# xbee_inclinometer.net
KiCad netlist of a schematic drawn in EAGLE
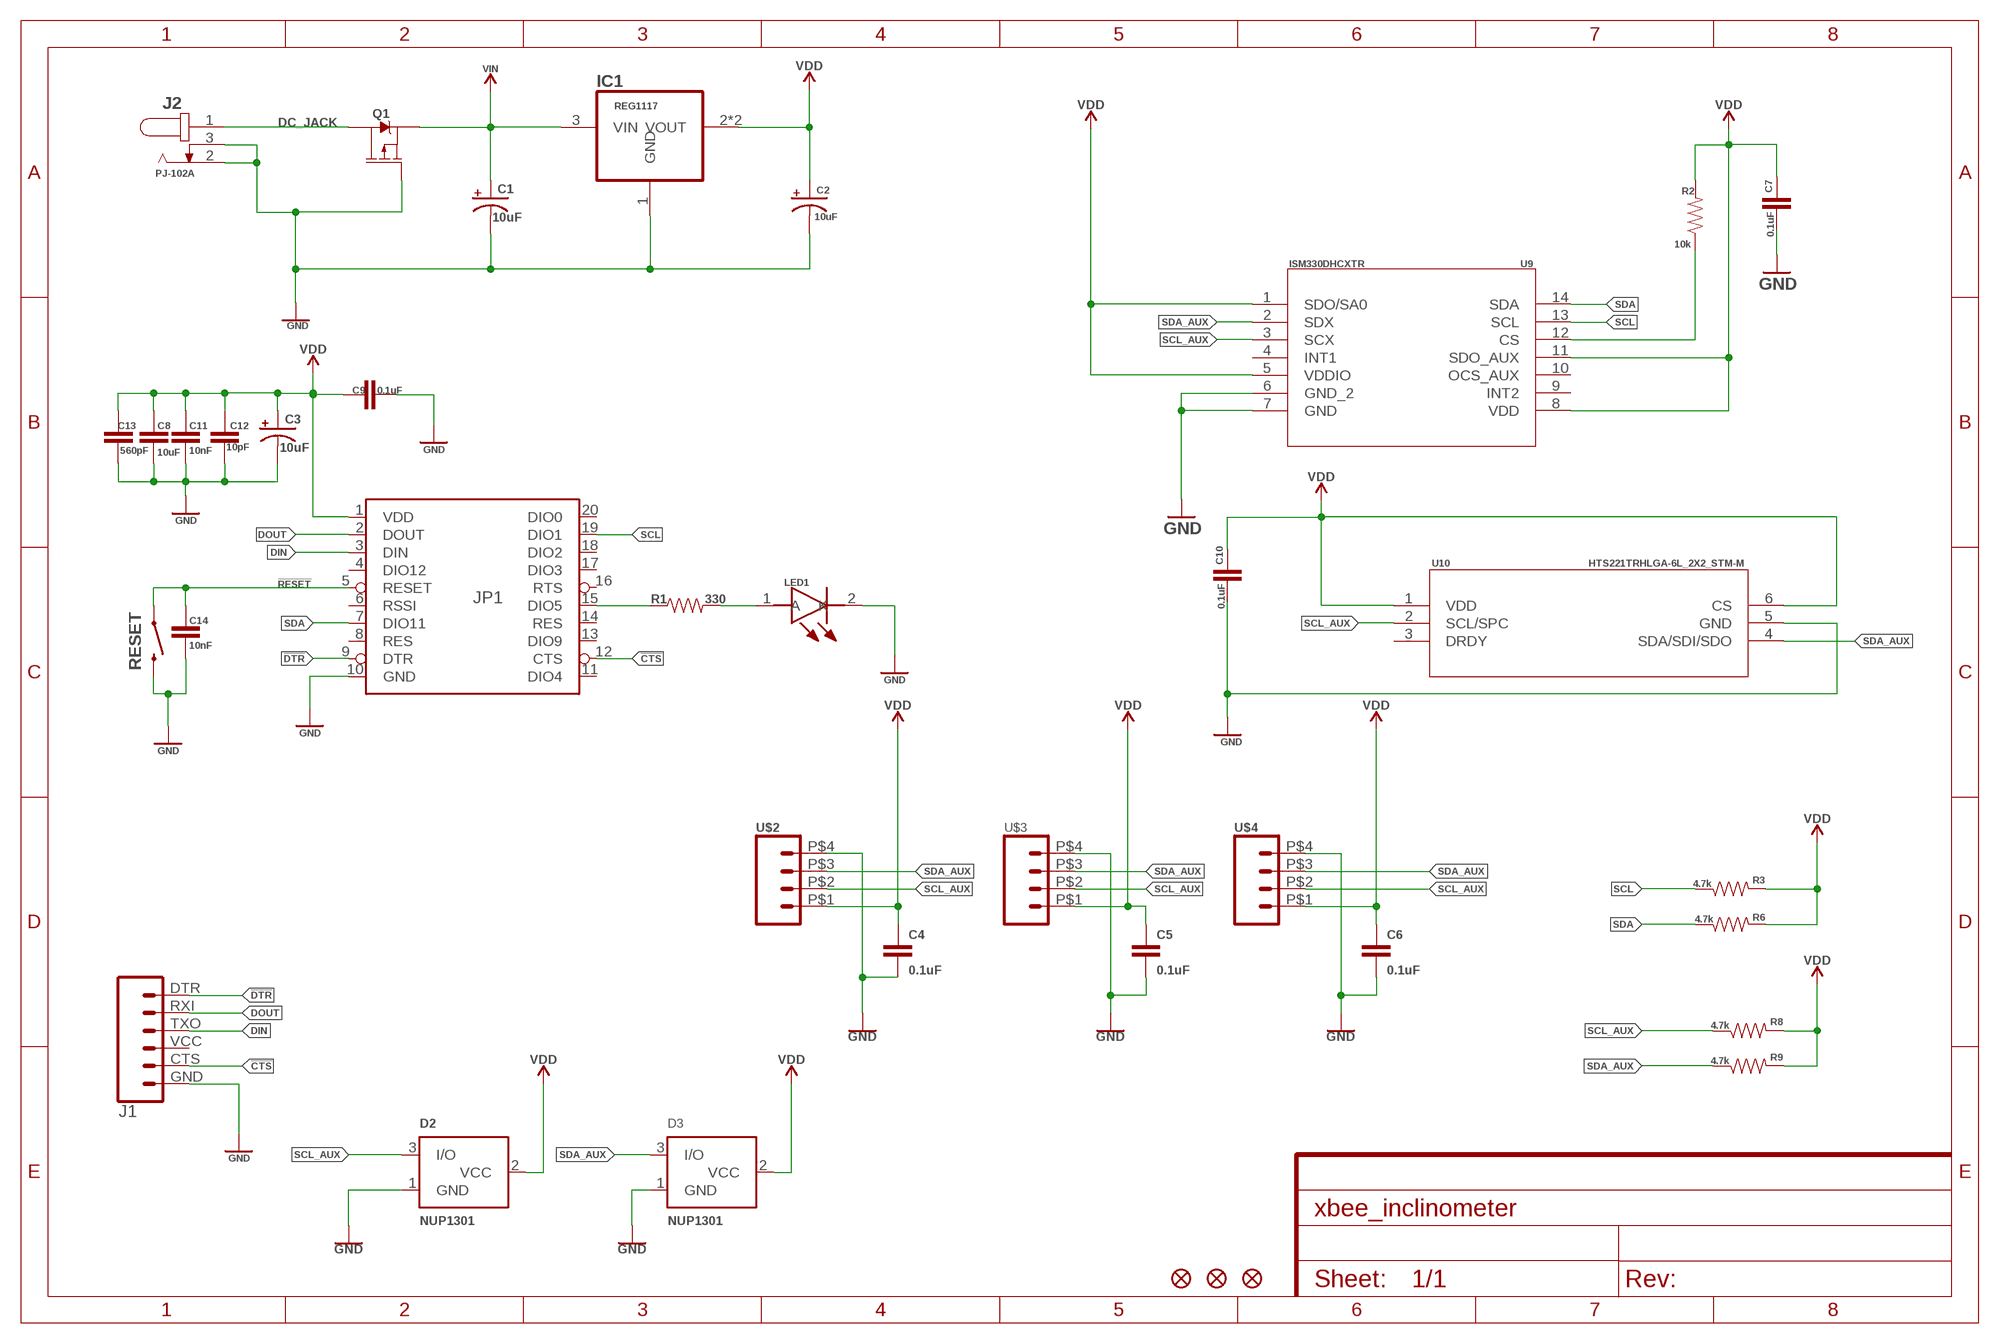
[diagram p0: schematic, sheet 1]

(export (version "E")
  (design (tool "Eeschema 10.0.6"))
  (components
    (comp (ref "C1")
      (value "10uF")
      (footprint "eagle-import:EIA3216")
      (libsource (lib "eagle-import") (part "10UF-POLAR-EIA3216-16V-10%(TANT)"))
    )
    (comp (ref "C2")
      (value "10uF")
      (footprint "eagle-import:EIA3216")
      (libsource (lib "eagle-import") (part "10UF-POLAR-EIA3216-16V-10%(TANT)"))
    )
    (comp (ref "C3")
      (value "10uF")
      (footprint "eagle-import:EIA3216")
      (libsource (lib "eagle-import") (part "10UF-POLAR-EIA3216-16V-10%(TANT)"))
    )
    (comp (ref "C4")
      (value "0.1uF")
      (footprint "eagle-import:0603")
      (libsource (lib "eagle-import") (part "0.1UF-0603-25V-(+80/-20%)"))
    )
    (comp (ref "C5")
      (value "0.1uF")
      (footprint "eagle-import:0603")
      (libsource (lib "eagle-import") (part "0.1UF-0603-25V-(+80/-20%)"))
    )
    (comp (ref "C6")
      (value "0.1uF")
      (footprint "eagle-import:0603")
      (libsource (lib "eagle-import") (part "0.1UF-0603-25V-(+80/-20%)"))
    )
    (comp (ref "C7")
      (value "0.1uF")
      (footprint "eagle-import:0603")
      (libsource (lib "eagle-import") (part "0.1UF-0603-25V-(+80/-20%)"))
    )
    (comp (ref "C8")
      (value "10uF")
      (footprint "eagle-import:0603")
      (libsource (lib "eagle-import") (part "10UF-0603-6.3V-20%"))
    )
    (comp (ref "C9")
      (value "0.1uF")
      (footprint "eagle-import:0603")
      (libsource (lib "eagle-import") (part "0.1UF-0603-25V-(+80/-20%)"))
    )
    (comp (ref "C10")
      (value "0.1uF")
      (footprint "eagle-import:0603")
      (libsource (lib "eagle-import") (part "0.1UF-0603-25V-(+80/-20%)"))
    )
    (comp (ref "C11")
      (value "10nF")
      (footprint "eagle-import:0603")
      (libsource (lib "eagle-import") (part "10NF-0603-50V-10%"))
    )
    (comp (ref "C12")
      (value "10pF")
      (footprint "eagle-import:0603")
      (libsource (lib "eagle-import") (part "10PF-0603-50V-5%"))
    )
    (comp (ref "C13")
      (value "560pF")
      (footprint "eagle-import:0603")
      (libsource (lib "eagle-import") (part "560PF-0603-50V-5%"))
    )
    (comp (ref "C14")
      (value "10nF")
      (footprint "eagle-import:0603")
      (libsource (lib "eagle-import") (part "10NF-0603-50V-10%"))
    )
    (comp (ref "D2")
      (value "NUP1301")
      (footprint "eagle-import:NUP1301_SOT-23")
      (libsource (lib "eagle-import") (part "NUP1301_NUP1301"))
    )
    (comp (ref "D3")
      (value "NUP1301")
      (footprint "eagle-import:NUP1301_SOT-23")
      (libsource (lib "eagle-import") (part "NUP1301_NUP1301"))
    )
    (comp (ref "FID1")
      (value "MICROBUILDER_FIDUCIAL\"\"")
      (footprint "eagle-import:MICROBUILDER_FIDUCIAL_1MM")
      (libsource (lib "eagle-import") (part "MICROBUILDER_FIDUCIAL{dblquote}{dblquote}"))
    )
    (comp (ref "FID2")
      (value "MICROBUILDER_FIDUCIAL\"\"")
      (footprint "eagle-import:MICROBUILDER_FIDUCIAL_1MM")
      (libsource (lib "eagle-import") (part "MICROBUILDER_FIDUCIAL{dblquote}{dblquote}"))
    )
    (comp (ref "FID4")
      (value "MICROBUILDER_FIDUCIAL\"\"")
      (footprint "eagle-import:MICROBUILDER_FIDUCIAL_1MM")
      (libsource (lib "eagle-import") (part "MICROBUILDER_FIDUCIAL{dblquote}{dblquote}"))
    )
    (comp (ref "IC1")
      (value "REG1117")
      (footprint "eagle-import:SOT223")
      (libsource (lib "eagle-import") (part "REG1117"))
    )
    (comp (ref "J1")
      (value "6_PIN_SERIAL_CABLEPTH")
      (footprint "eagle-import:FTDI_BASIC")
      (libsource (lib "eagle-import") (part "6_PIN_SERIAL_CABLEPTH"))
    )
    (comp (ref "J2")
      (value "PJ-102A")
      (footprint "eagle-import:CUI_PJ-102A")
      (fields (field (name "MANUFACTURER") "CUI INC"))
      (libsource (lib "eagle-import") (part "PJ-102A"))
    )
    (comp (ref "JP1")
      (value "XBEESMD")
      (footprint "eagle-import:XBEE-SMD")
      (libsource (lib "eagle-import") (part "XBEESMD"))
    )
    (comp (ref "LED1")
      (value "SMTL2-UWD")
      (footprint "eagle-import:SMTL2UWD")
      (fields (field (name "MOUSER_PART_NUMBER") "749-SMTL2-UWD"))
      (libsource (lib "eagle-import") (part "SMTL2-UWD"))
    )
    (comp (ref "Q1")
      (value "2.5A/30V/105mΩ")
      (footprint "eagle-import:SOT23-3")
      (libsource (lib "eagle-import") (part "MOSFET_PCH-DMG2307L"))
    )
    (comp (ref "R1")
      (value "330")
      (footprint "eagle-import:0603")
      (libsource (lib "eagle-import") (part "330OHM-0603-1/10W-1%"))
    )
    (comp (ref "R2")
      (value "10k")
      (footprint "eagle-import:0603")
      (libsource (lib "eagle-import") (part "10KOHM-0603-1/10W-1%"))
    )
    (comp (ref "R3")
      (value "4.7k")
      (footprint "eagle-import:0603")
      (libsource (lib "eagle-import") (part "4.7KOHM-0603-1/10W-1%"))
    )
    (comp (ref "R6")
      (value "4.7k")
      (footprint "eagle-import:0603")
      (libsource (lib "eagle-import") (part "4.7KOHM-0603-1/10W-1%"))
    )
    (comp (ref "R8")
      (value "4.7k")
      (footprint "eagle-import:0603")
      (libsource (lib "eagle-import") (part "4.7KOHM-0603-1/10W-1%"))
    )
    (comp (ref "R9")
      (value "4.7k")
      (footprint "eagle-import:0603")
      (libsource (lib "eagle-import") (part "4.7KOHM-0603-1/10W-1%"))
    )
    (comp (ref "RESET")
      (value "MOMENTARY-SWITCH-SPST-PTH-6.0MM")
      (footprint "eagle-import:TACTILE_SWITCH_PTH_6.0MM")
      (libsource (lib "eagle-import") (part "MOMENTARY-SWITCH-SPST-PTH-6.0MM"))
    )
    (comp (ref "U$2")
      (value "RIGHT_ANGLED_DCFRECONN")
      (footprint "eagle-import:M8_FRECONN")
      (libsource (lib "eagle-import") (part "RIGHT_ANGLED_DCFRECONN"))
    )
    (comp (ref "U$3")
      (value "RIGHT_ANGLED_DCFRECONN")
      (footprint "eagle-import:M8_FRECONN")
      (libsource (lib "eagle-import") (part "RIGHT_ANGLED_DCFRECONN"))
    )
    (comp (ref "U$4")
      (value "RIGHT_ANGLED_DCFRECONN")
      (footprint "eagle-import:M8_FRECONN")
      (libsource (lib "eagle-import") (part "RIGHT_ANGLED_DCFRECONN"))
    )
    (comp (ref "U9")
      (value "ISM330DHCXTR")
      (footprint "eagle-import:QFN_DHCXTR_STM")
      (fields (field (name "COPYRIGHT") "Copyright (C) 2018 Accelerated Designs. All rights reserved"))
      (libsource (lib "eagle-import") (part "ISM330DHCXTR"))
    )
    (comp (ref "U10")
      (value "HTS221TRHLGA-6L_2X2_STM-M")
      (footprint "eagle-import:HLGA-6L_2X2_STM-M")
      (fields
        (field (name "MANUFACTURER_PART_NUMBER") "HTS221TR")
        (field (name "COPYRIGHT") "Copyright (C) 2018 Accelerated Designs. All rights reserved")
      )
      (libsource (lib "eagle-import") (part "HTS221TRHLGA-6L_2X2_STM-M"))
    )
  )
  (nets
    (net (code "1") (name "/DC_JACK") (class "Default")
      (node (ref "J2") (pin "1") (pinfunction "1_1") (pintype "passive"))
      (node (ref "Q1") (pin "3") (pinfunction "D_3") (pintype "bidirectional"))
    )
    (net (code "2") (name "/~{CTS}") (class "Default")
      (node (ref "J1") (pin "CTS") (pinfunction "5_CTS") (pintype "passive"))
      (node (ref "JP1") (pin "12") (pinfunction "CTS_12") (pintype "output"))
    )
    (net (code "3") (name "/~{DTR}") (class "Default")
      (node (ref "J1") (pin "DTR") (pinfunction "1_DTR") (pintype "passive"))
      (node (ref "JP1") (pin "9") (pinfunction "DTR_9") (pintype "bidirectional"))
    )
    (net (code "4") (name "/~{RESET}") (class "Default")
      (node (ref "C14") (pin "1") (pinfunction "1_1") (pintype "passive"))
      (node (ref "JP1") (pin "5") (pinfunction "RESET_5") (pintype "input"))
      (node (ref "RESET") (pin "1") (pinfunction "1_1") (pintype "passive"))
    )
    (net (code "5") (name "DIN") (class "Default")
      (node (ref "J1") (pin "TXO") (pinfunction "3_TXO") (pintype "passive"))
      (node (ref "JP1") (pin "3") (pinfunction "DIN_3") (pintype "input"))
    )
    (net (code "6") (name "DOUT") (class "Default")
      (node (ref "J1") (pin "RXI") (pinfunction "2_RXI") (pintype "passive"))
      (node (ref "JP1") (pin "2") (pinfunction "DOUT_2") (pintype "output"))
    )
    (net (code "7") (name "GND") (class "Default")
      (node (ref "C1") (pin "-") (pinfunction "-_-") (pintype "passive"))
      (node (ref "C10") (pin "2") (pinfunction "2_2") (pintype "passive"))
      (node (ref "C11") (pin "2") (pinfunction "2_2") (pintype "passive"))
      (node (ref "C12") (pin "2") (pinfunction "2_2") (pintype "passive"))
      (node (ref "C13") (pin "2") (pinfunction "2_2") (pintype "passive"))
      (node (ref "C14") (pin "2") (pinfunction "2_2") (pintype "passive"))
      (node (ref "C2") (pin "-") (pinfunction "-_-") (pintype "passive"))
      (node (ref "C3") (pin "-") (pinfunction "-_-") (pintype "passive"))
      (node (ref "C4") (pin "2") (pinfunction "2_2") (pintype "passive"))
      (node (ref "C5") (pin "2") (pinfunction "2_2") (pintype "passive"))
      (node (ref "C6") (pin "2") (pinfunction "2_2") (pintype "passive"))
      (node (ref "C7") (pin "2") (pinfunction "2_2") (pintype "passive"))
      (node (ref "C8") (pin "2") (pinfunction "2_2") (pintype "passive"))
      (node (ref "C9") (pin "1") (pinfunction "1_1") (pintype "passive"))
      (node (ref "D2") (pin "1") (pinfunction "GND_1") (pintype "power_in"))
      (node (ref "D3") (pin "1") (pinfunction "GND_1") (pintype "power_in"))
      (node (ref "IC1") (pin "1") (pinfunction "GND_1") (pintype "power_in"))
      (node (ref "J1") (pin "GND") (pinfunction "6_GND") (pintype "passive"))
      (node (ref "J2") (pin "2") (pinfunction "2_2") (pintype "passive"))
      (node (ref "J2") (pin "3") (pinfunction "3_3") (pintype "passive"))
      (node (ref "JP1") (pin "10") (pinfunction "GND_10") (pintype "power_in"))
      (node (ref "LED1") (pin "2") (pinfunction "K_2") (pintype "bidirectional"))
      (node (ref "Q1") (pin "1") (pinfunction "G_1") (pintype "bidirectional"))
      (node (ref "RESET") (pin "3") (pinfunction "2_3") (pintype "passive"))
      (node (ref "U$2") (pin "P$4") (pinfunction "GND_P$4") (pintype "passive"))
      (node (ref "U$3") (pin "P$4") (pinfunction "GND_P$4") (pintype "passive"))
      (node (ref "U$4") (pin "P$4") (pinfunction "GND_P$4") (pintype "passive"))
      (node (ref "U10") (pin "5") (pinfunction "GND_5") (pintype "passive"))
      (node (ref "U9") (pin "6") (pinfunction "GND_2_6") (pintype "passive"))
      (node (ref "U9") (pin "7") (pinfunction "GND_7") (pintype "passive"))
    )
    (net (code "8") (name "Net-(JP1-DIO5)") (class "Default")
      (node (ref "JP1") (pin "15") (pinfunction "DIO5_15") (pintype "bidirectional"))
      (node (ref "R1") (pin "1") (pinfunction "1_1") (pintype "passive"))
    )
    (net (code "9") (name "Net-(LED1-A)") (class "Default")
      (node (ref "LED1") (pin "1") (pinfunction "A_1") (pintype "bidirectional"))
      (node (ref "R1") (pin "2") (pinfunction "2_2") (pintype "passive"))
    )
    (net (code "10") (name "Net-(U9-CS)") (class "Default")
      (node (ref "R2") (pin "1") (pinfunction "1_1") (pintype "passive"))
      (node (ref "U9") (pin "12") (pinfunction "CS_12") (pintype "passive"))
    )
    (net (code "11") (name "SCL") (class "Default")
      (node (ref "JP1") (pin "19") (pinfunction "DIO1_19") (pintype "bidirectional"))
      (node (ref "R3") (pin "1") (pinfunction "1_1") (pintype "passive"))
      (node (ref "U9") (pin "13") (pinfunction "SCL_13") (pintype "passive"))
    )
    (net (code "12") (name "SCL_AUX") (class "Default")
      (node (ref "D2") (pin "3") (pinfunction "I/O_3") (pintype "bidirectional"))
      (node (ref "R8") (pin "1") (pinfunction "1_1") (pintype "passive"))
      (node (ref "U$2") (pin "P$2") (pinfunction "SCL_P$2") (pintype "passive"))
      (node (ref "U$3") (pin "P$2") (pinfunction "SCL_P$2") (pintype "passive"))
      (node (ref "U$4") (pin "P$2") (pinfunction "SCL_P$2") (pintype "passive"))
      (node (ref "U10") (pin "2") (pinfunction "SCL/SPC_2") (pintype "passive"))
      (node (ref "U9") (pin "3") (pinfunction "SCX_3") (pintype "passive"))
    )
    (net (code "13") (name "SDA") (class "Default")
      (node (ref "JP1") (pin "7") (pinfunction "DIO11_7") (pintype "bidirectional"))
      (node (ref "R6") (pin "1") (pinfunction "1_1") (pintype "passive"))
      (node (ref "U9") (pin "14") (pinfunction "SDA_14") (pintype "passive"))
    )
    (net (code "14") (name "SDA_AUX") (class "Default")
      (node (ref "D3") (pin "3") (pinfunction "I/O_3") (pintype "bidirectional"))
      (node (ref "R9") (pin "1") (pinfunction "1_1") (pintype "passive"))
      (node (ref "U$2") (pin "P$3") (pinfunction "SDA_P$3") (pintype "passive"))
      (node (ref "U$3") (pin "P$3") (pinfunction "SDA_P$3") (pintype "passive"))
      (node (ref "U$4") (pin "P$3") (pinfunction "SDA_P$3") (pintype "passive"))
      (node (ref "U10") (pin "4") (pinfunction "SDA/SDI/SDO_4") (pintype "passive"))
      (node (ref "U9") (pin "2") (pinfunction "SDX_2") (pintype "passive"))
    )
    (net (code "15") (name "VDD") (class "Default")
      (node (ref "C10") (pin "1") (pinfunction "1_1") (pintype "passive"))
      (node (ref "C11") (pin "1") (pinfunction "1_1") (pintype "passive"))
      (node (ref "C12") (pin "1") (pinfunction "1_1") (pintype "passive"))
      (node (ref "C13") (pin "1") (pinfunction "1_1") (pintype "passive"))
      (node (ref "C2") (pin "+") (pinfunction "+_+") (pintype "passive"))
      (node (ref "C3") (pin "+") (pinfunction "+_+") (pintype "passive"))
      (node (ref "C4") (pin "1") (pinfunction "1_1") (pintype "passive"))
      (node (ref "C5") (pin "1") (pinfunction "1_1") (pintype "passive"))
      (node (ref "C6") (pin "1") (pinfunction "1_1") (pintype "passive"))
      (node (ref "C7") (pin "1") (pinfunction "1_1") (pintype "passive"))
      (node (ref "C8") (pin "1") (pinfunction "1_1") (pintype "passive"))
      (node (ref "C9") (pin "2") (pinfunction "2_2") (pintype "passive"))
      (node (ref "D2") (pin "2") (pinfunction "VCC_2") (pintype "power_in"))
      (node (ref "D3") (pin "2") (pinfunction "VCC_2") (pintype "power_in"))
      (node (ref "IC1") (pin "2") (pinfunction "VOUT_2") (pintype "output"))
      (node (ref "IC1") (pin "4") (pinfunction "VOUT_4") (pintype "output"))
      (node (ref "JP1") (pin "1") (pinfunction "VDD_1") (pintype "power_in"))
      (node (ref "R2") (pin "2") (pinfunction "2_2") (pintype "passive"))
      (node (ref "R3") (pin "2") (pinfunction "2_2") (pintype "passive"))
      (node (ref "R6") (pin "2") (pinfunction "2_2") (pintype "passive"))
      (node (ref "R8") (pin "2") (pinfunction "2_2") (pintype "passive"))
      (node (ref "R9") (pin "2") (pinfunction "2_2") (pintype "passive"))
      (node (ref "U$2") (pin "P$1") (pinfunction "VCC_P$1") (pintype "passive"))
      (node (ref "U$3") (pin "P$1") (pinfunction "VCC_P$1") (pintype "passive"))
      (node (ref "U$4") (pin "P$1") (pinfunction "VCC_P$1") (pintype "passive"))
      (node (ref "U10") (pin "1") (pinfunction "VDD_1") (pintype "power_in"))
      (node (ref "U10") (pin "6") (pinfunction "CS_6") (pintype "passive"))
      (node (ref "U9") (pin "1") (pinfunction "SDO/SA0_1") (pintype "passive"))
      (node (ref "U9") (pin "11") (pinfunction "SDO_AUX_11") (pintype "passive"))
      (node (ref "U9") (pin "5") (pinfunction "VDDIO_5") (pintype "power_in"))
      (node (ref "U9") (pin "8") (pinfunction "VDD_8") (pintype "power_in"))
    )
    (net (code "16") (name "VIN") (class "Default")
      (node (ref "C1") (pin "+") (pinfunction "+_+") (pintype "passive"))
      (node (ref "IC1") (pin "3") (pinfunction "VIN_3") (pintype "input"))
      (node (ref "Q1") (pin "2") (pinfunction "S_2") (pintype "bidirectional"))
    )
    (net (code "17") (name "unconnected-(J1-4-PadVCC)") (class "Default")
      (node (ref "J1") (pin "VCC") (pinfunction "4_VCC") (pintype "passive"))
    )
    (net (code "18") (name "unconnected-(JP1-DIO0-Pad20)") (class "Default")
      (node (ref "JP1") (pin "20") (pinfunction "DIO0_20") (pintype "bidirectional"))
    )
    (net (code "19") (name "unconnected-(JP1-DIO2-Pad18)") (class "Default")
      (node (ref "JP1") (pin "18") (pinfunction "DIO2_18") (pintype "bidirectional"))
    )
    (net (code "20") (name "unconnected-(JP1-DIO3-Pad17)") (class "Default")
      (node (ref "JP1") (pin "17") (pinfunction "DIO3_17") (pintype "bidirectional"))
    )
    (net (code "21") (name "unconnected-(JP1-DIO4-Pad11)") (class "Default")
      (node (ref "JP1") (pin "11") (pinfunction "DIO4_11") (pintype "bidirectional"))
    )
    (net (code "22") (name "unconnected-(JP1-DIO9-Pad13)") (class "Default")
      (node (ref "JP1") (pin "13") (pinfunction "DIO9_13") (pintype "bidirectional"))
    )
    (net (code "23") (name "unconnected-(JP1-DIO12-Pad4)") (class "Default")
      (node (ref "JP1") (pin "4") (pinfunction "DIO12_4") (pintype "bidirectional"))
    )
    (net (code "24") (name "unconnected-(JP1-RES-Pad8)") (class "Default")
      (node (ref "JP1") (pin "8") (pinfunction "RES_8") (pintype "bidirectional"))
    )
    (net (code "25") (name "unconnected-(JP1-RES-Pad14)") (class "Default")
      (node (ref "JP1") (pin "14") (pinfunction "RES_14") (pintype "bidirectional"))
    )
    (net (code "26") (name "unconnected-(JP1-RSSI-Pad6)") (class "Default")
      (node (ref "JP1") (pin "6") (pinfunction "RSSI_6") (pintype "bidirectional"))
    )
    (net (code "27") (name "unconnected-(JP1-RTS-Pad16)") (class "Default")
      (node (ref "JP1") (pin "16") (pinfunction "RTS_16") (pintype "input"))
    )
    (net (code "28") (name "unconnected-(U9-INT1-Pad4)") (class "Default")
      (node (ref "U9") (pin "4") (pinfunction "INT1_4") (pintype "input"))
    )
    (net (code "29") (name "unconnected-(U9-INT2-Pad9)") (class "Default")
      (node (ref "U9") (pin "9") (pinfunction "INT2_9") (pintype "input"))
    )
    (net (code "30") (name "unconnected-(U9-OCS_AUX-Pad10)") (class "Default")
      (node (ref "U9") (pin "10") (pinfunction "OCS_AUX_10") (pintype "passive"))
    )
    (net (code "31") (name "unconnected-(U10-DRDY-Pad3)") (class "Default")
      (node (ref "U10") (pin "3") (pinfunction "DRDY_3") (pintype "passive"))
    )
  )
)
